# X-A4U-stick.net
KiCad netlist of a schematic drawn in EAGLE
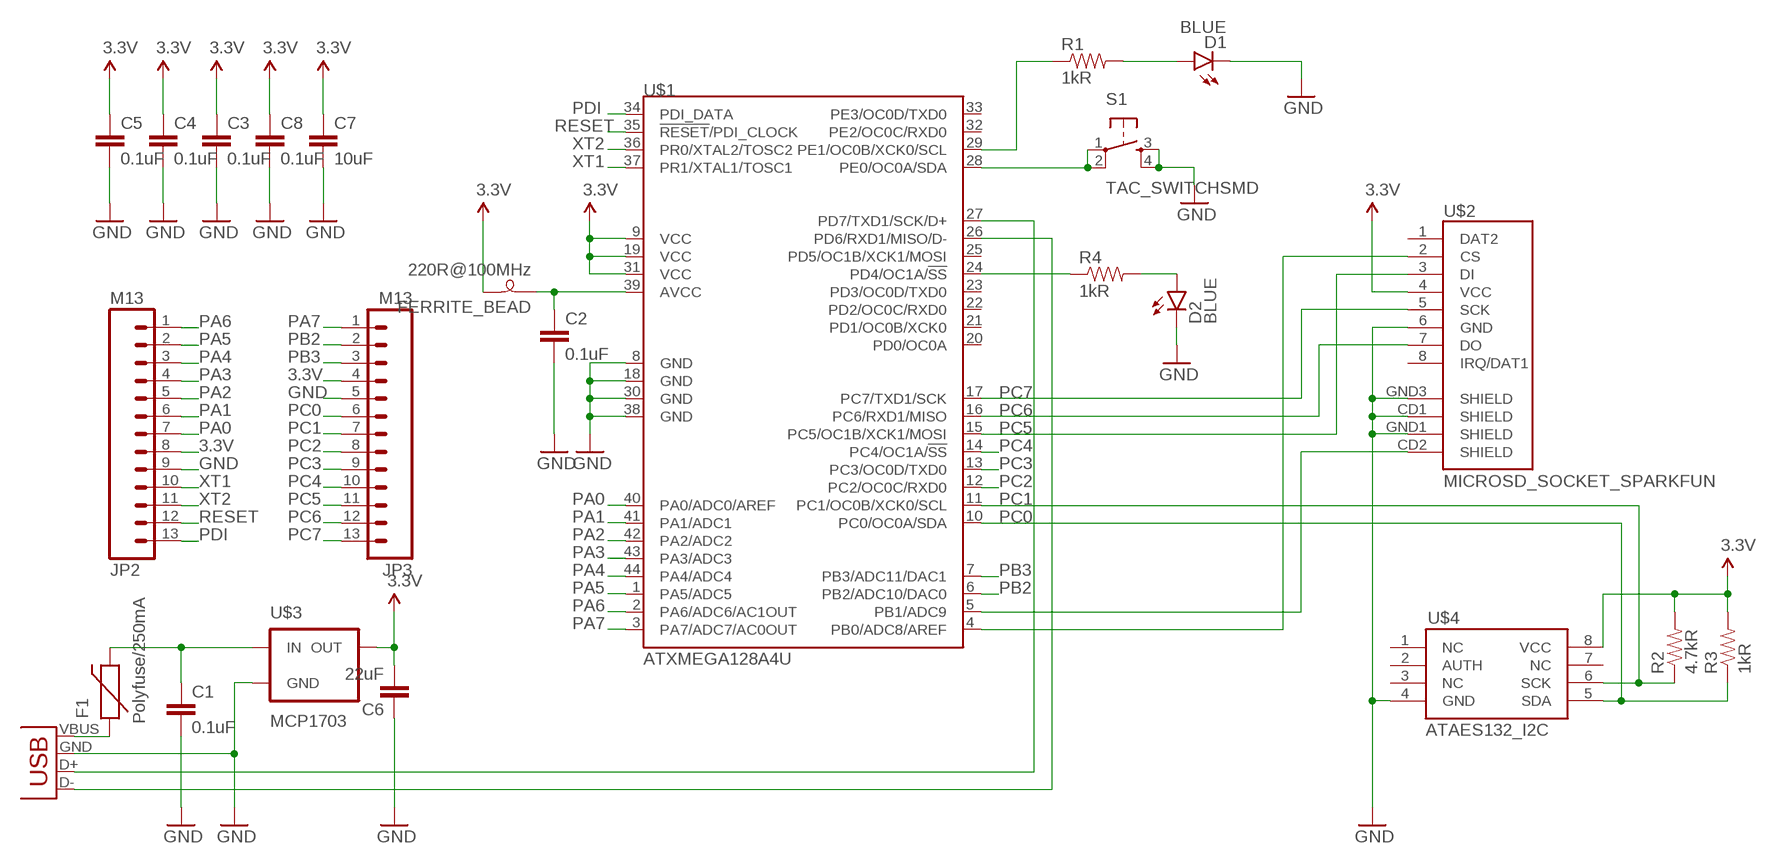
[diagram p0: schematic, sheet 1]

(export (version "E")
  (design (tool "Eeschema 10.0.6"))
  (components
    (comp (ref "C1")
      (value "0.1uF")
      (footprint "eagle-import:0805")
      (libsource (lib "eagle-import") (part "CAP0805"))
    )
    (comp (ref "C2")
      (value "0.1uF")
      (footprint "eagle-import:0805")
      (libsource (lib "eagle-import") (part "CAP0805"))
    )
    (comp (ref "C3")
      (value "0.1uF")
      (footprint "eagle-import:0805")
      (libsource (lib "eagle-import") (part "CAP0805"))
    )
    (comp (ref "C4")
      (value "0.1uF")
      (footprint "eagle-import:0805")
      (libsource (lib "eagle-import") (part "CAP0805"))
    )
    (comp (ref "C5")
      (value "0.1uF")
      (footprint "eagle-import:0805")
      (libsource (lib "eagle-import") (part "CAP0805"))
    )
    (comp (ref "C6")
      (value "22uF")
      (footprint "eagle-import:1206")
      (libsource (lib "eagle-import") (part "CAP1206"))
    )
    (comp (ref "C7")
      (value "10uF")
      (footprint "eagle-import:1206")
      (libsource (lib "eagle-import") (part "CAP1206"))
    )
    (comp (ref "C8")
      (value "0.1uF")
      (footprint "eagle-import:1206")
      (libsource (lib "eagle-import") (part "CAP1206"))
    )
    (comp (ref "D1")
      (value "BLUE")
      (footprint "eagle-import:LED-1206")
      (libsource (lib "eagle-import") (part "LED-BLUE1206"))
    )
    (comp (ref "D2")
      (value "BLUE")
      (footprint "eagle-import:LED-1206")
      (libsource (lib "eagle-import") (part "LED-BLUE1206"))
    )
    (comp (ref "F1")
      (value "Polyfuse/250mA")
      (footprint "eagle-import:PTC-1206-WIDE")
      (libsource (lib "eagle-import") (part "PTCSMD-W"))
    )
    (comp (ref "FERRITE_BEAD")
      (value "220R@100MHz")
      (footprint "eagle-import:0805")
      (libsource (lib "eagle-import") (part "FERRITE-BEAD0805"))
    )
    (comp (ref "JP1")
      (value "USB-A-H")
      (footprint "eagle-import:USB-A-H")
      (libsource (lib "eagle-import") (part "USB-A-H"))
    )
    (comp (ref "JP2")
      (value "M13")
      (footprint "eagle-import:1X13")
      (libsource (lib "eagle-import") (part "M13"))
    )
    (comp (ref "JP3")
      (value "M13")
      (footprint "eagle-import:1X13")
      (libsource (lib "eagle-import") (part "M13"))
    )
    (comp (ref "R1")
      (value "1kR")
      (footprint "eagle-import:1206")
      (libsource (lib "eagle-import") (part "RESISTOR1206"))
    )
    (comp (ref "R2")
      (value "4.7kR")
      (footprint "eagle-import:1206")
      (libsource (lib "eagle-import") (part "RESISTOR1206"))
    )
    (comp (ref "R3")
      (value "1kR")
      (footprint "eagle-import:1206")
      (libsource (lib "eagle-import") (part "RESISTOR1206"))
    )
    (comp (ref "R4")
      (value "1kR")
      (footprint "eagle-import:1206")
      (libsource (lib "eagle-import") (part "RESISTOR1206"))
    )
    (comp (ref "S1")
      (value "TAC_SWITCHSMD")
      (footprint "eagle-import:TACTILE-SWITCH-SMD")
      (libsource (lib "eagle-import") (part "TAC_SWITCHSMD"))
    )
    (comp (ref "U$1")
      (value "ATXMEGA128A4U")
      (footprint "eagle-import:TQFP-44")
      (libsource (lib "eagle-import") (part "ATXMEGA128A4U"))
    )
    (comp (ref "U$2")
      (value "MICROSD_SOCKET_SPARKFUN")
      (footprint "eagle-import:MICROSD_SOCKET_SPARKFUN")
      (libsource (lib "eagle-import") (part "MICROSD_SOCKET_SPARKFUN"))
    )
    (comp (ref "U$3")
      (value "MCP1703")
      (footprint "eagle-import:SOT-89")
      (libsource (lib "eagle-import") (part "MCP1703"))
    )
    (comp (ref "U$4")
      (value "ATAES132_I2C")
      (footprint "eagle-import:SOIC-8-NARROW")
      (libsource (lib "eagle-import") (part "ATAES132_I2C"))
    )
  )
  (nets
    (net (code "1") (name "/PA0") (class "Default")
      (node (ref "JP2") (pin "7") (pinfunction "7_7") (pintype "passive"))
      (node (ref "U$1") (pin "40") (pinfunction "PA0/ADC0/AREF_40") (pintype "bidirectional"))
    )
    (net (code "2") (name "/PA1") (class "Default")
      (node (ref "JP2") (pin "6") (pinfunction "6_6") (pintype "passive"))
      (node (ref "U$1") (pin "41") (pinfunction "PA1/ADC1_41") (pintype "bidirectional"))
    )
    (net (code "3") (name "/PA2") (class "Default")
      (node (ref "JP2") (pin "5") (pinfunction "5_5") (pintype "passive"))
      (node (ref "U$1") (pin "42") (pinfunction "PA2/ADC2_42") (pintype "bidirectional"))
    )
    (net (code "4") (name "/PA3") (class "Default")
      (node (ref "JP2") (pin "4") (pinfunction "4_4") (pintype "passive"))
      (node (ref "U$1") (pin "43") (pinfunction "PA3/ADC3_43") (pintype "bidirectional"))
    )
    (net (code "5") (name "/PA4") (class "Default")
      (node (ref "JP2") (pin "3") (pinfunction "3_3") (pintype "passive"))
      (node (ref "U$1") (pin "44") (pinfunction "PA4/ADC4_44") (pintype "bidirectional"))
    )
    (net (code "6") (name "/PA5") (class "Default")
      (node (ref "JP2") (pin "2") (pinfunction "2_2") (pintype "passive"))
      (node (ref "U$1") (pin "1") (pinfunction "PA5/ADC5_1") (pintype "bidirectional"))
    )
    (net (code "7") (name "/PA6") (class "Default")
      (node (ref "JP2") (pin "1") (pinfunction "1_1") (pintype "passive"))
      (node (ref "U$1") (pin "2") (pinfunction "PA6/ADC6/AC1OUT_2") (pintype "bidirectional"))
    )
    (net (code "8") (name "/PA7") (class "Default")
      (node (ref "JP3") (pin "1") (pinfunction "1_1") (pintype "passive"))
      (node (ref "U$1") (pin "3") (pinfunction "PA7/ADC7/AC0OUT_3") (pintype "bidirectional"))
    )
    (net (code "9") (name "/PB2") (class "Default")
      (node (ref "JP3") (pin "2") (pinfunction "2_2") (pintype "passive"))
      (node (ref "U$1") (pin "6") (pinfunction "PB2/ADC10/DAC0_6") (pintype "bidirectional"))
    )
    (net (code "10") (name "/PB3") (class "Default")
      (node (ref "JP3") (pin "3") (pinfunction "3_3") (pintype "passive"))
      (node (ref "U$1") (pin "7") (pinfunction "PB3/ADC11/DAC1_7") (pintype "bidirectional"))
    )
    (net (code "11") (name "/PC0") (class "Default")
      (node (ref "JP3") (pin "6") (pinfunction "6_6") (pintype "passive"))
      (node (ref "R3") (pin "1") (pinfunction "1_1") (pintype "passive"))
      (node (ref "U$1") (pin "10") (pinfunction "PC0/OC0A/SDA_10") (pintype "bidirectional"))
      (node (ref "U$4") (pin "5") (pinfunction "SDA_5") (pintype "bidirectional"))
    )
    (net (code "12") (name "/PC1") (class "Default")
      (node (ref "JP3") (pin "7") (pinfunction "7_7") (pintype "passive"))
      (node (ref "R2") (pin "1") (pinfunction "1_1") (pintype "passive"))
      (node (ref "U$1") (pin "11") (pinfunction "PC1/OC0B/XCK0/SCL_11") (pintype "bidirectional"))
      (node (ref "U$4") (pin "6") (pinfunction "SCK_6") (pintype "input"))
    )
    (net (code "13") (name "/PC2") (class "Default")
      (node (ref "JP3") (pin "8") (pinfunction "8_8") (pintype "passive"))
      (node (ref "U$1") (pin "12") (pinfunction "PC2/OC0C/RXD0_12") (pintype "bidirectional"))
    )
    (net (code "14") (name "/PC3") (class "Default")
      (node (ref "JP3") (pin "9") (pinfunction "9_9") (pintype "passive"))
      (node (ref "U$1") (pin "13") (pinfunction "PC3/OC0D/TXD0_13") (pintype "bidirectional"))
    )
    (net (code "15") (name "/PC4") (class "Default")
      (node (ref "JP3") (pin "10") (pinfunction "10_10") (pintype "passive"))
      (node (ref "U$1") (pin "14") (pinfunction "PC4/OC1A/~{SS}_14") (pintype "bidirectional"))
    )
    (net (code "16") (name "/PC5") (class "Default")
      (node (ref "JP3") (pin "11") (pinfunction "11_11") (pintype "passive"))
      (node (ref "U$1") (pin "15") (pinfunction "PC5/OC1B/XCK1/MOSI_15") (pintype "bidirectional"))
      (node (ref "U$2") (pin "3") (pinfunction "DI_3") (pintype "bidirectional"))
    )
    (net (code "17") (name "/PC6") (class "Default")
      (node (ref "JP3") (pin "12") (pinfunction "12_12") (pintype "passive"))
      (node (ref "U$1") (pin "16") (pinfunction "PC6/RXD1/MISO_16") (pintype "bidirectional"))
      (node (ref "U$2") (pin "7") (pinfunction "DO_7") (pintype "bidirectional"))
    )
    (net (code "18") (name "/PC7") (class "Default")
      (node (ref "JP3") (pin "13") (pinfunction "13_13") (pintype "passive"))
      (node (ref "U$1") (pin "17") (pinfunction "PC7/TXD1/SCK_17") (pintype "bidirectional"))
      (node (ref "U$2") (pin "5") (pinfunction "SCK_5") (pintype "bidirectional"))
    )
    (net (code "19") (name "/PDI") (class "Default")
      (node (ref "JP2") (pin "13") (pinfunction "13_13") (pintype "passive"))
      (node (ref "U$1") (pin "34") (pinfunction "PDI_DATA_34") (pintype "bidirectional"))
    )
    (net (code "20") (name "/RESET") (class "Default")
      (node (ref "JP2") (pin "12") (pinfunction "12_12") (pintype "passive"))
      (node (ref "U$1") (pin "35") (pinfunction "~{RESET}/PDI_CLOCK_35") (pintype "bidirectional"))
    )
    (net (code "21") (name "/XT1") (class "Default")
      (node (ref "JP2") (pin "10") (pinfunction "10_10") (pintype "passive"))
      (node (ref "U$1") (pin "37") (pinfunction "PR1/XTAL1/TOSC1_37") (pintype "bidirectional"))
    )
    (net (code "22") (name "/XT2") (class "Default")
      (node (ref "JP2") (pin "11") (pinfunction "11_11") (pintype "passive"))
      (node (ref "U$1") (pin "36") (pinfunction "PR0/XTAL2/TOSC2_36") (pintype "bidirectional"))
    )
    (net (code "23") (name "3.3V") (class "Default")
      (node (ref "C3") (pin "1") (pinfunction "1_1") (pintype "passive"))
      (node (ref "C4") (pin "1") (pinfunction "1_1") (pintype "passive"))
      (node (ref "C5") (pin "1") (pinfunction "1_1") (pintype "passive"))
      (node (ref "C6") (pin "2") (pinfunction "2_2") (pintype "passive"))
      (node (ref "C7") (pin "1") (pinfunction "1_1") (pintype "passive"))
      (node (ref "C8") (pin "1") (pinfunction "1_1") (pintype "passive"))
      (node (ref "FERRITE_BEAD") (pin "2") (pinfunction "2_2") (pintype "passive"))
      (node (ref "JP2") (pin "8") (pinfunction "8_8") (pintype "passive"))
      (node (ref "JP3") (pin "4") (pinfunction "4_4") (pintype "passive"))
      (node (ref "R2") (pin "2") (pinfunction "2_2") (pintype "passive"))
      (node (ref "R3") (pin "2") (pinfunction "2_2") (pintype "passive"))
      (node (ref "U$1") (pin "19") (pinfunction "VCC_19") (pintype "bidirectional"))
      (node (ref "U$1") (pin "31") (pinfunction "VCC_31") (pintype "bidirectional"))
      (node (ref "U$1") (pin "9") (pinfunction "VCC_9") (pintype "bidirectional"))
      (node (ref "U$2") (pin "4") (pinfunction "VCC_4") (pintype "bidirectional"))
      (node (ref "U$3") (pin "3") (pinfunction "OUT_3") (pintype "passive"))
      (node (ref "U$4") (pin "8") (pinfunction "VCC_8") (pintype "bidirectional"))
    )
    (net (code "24") (name "GND") (class "Default")
      (node (ref "C1") (pin "2") (pinfunction "2_2") (pintype "passive"))
      (node (ref "C2") (pin "2") (pinfunction "2_2") (pintype "passive"))
      (node (ref "C3") (pin "2") (pinfunction "2_2") (pintype "passive"))
      (node (ref "C4") (pin "2") (pinfunction "2_2") (pintype "passive"))
      (node (ref "C5") (pin "2") (pinfunction "2_2") (pintype "passive"))
      (node (ref "C6") (pin "1") (pinfunction "1_1") (pintype "passive"))
      (node (ref "C7") (pin "2") (pinfunction "2_2") (pintype "passive"))
      (node (ref "C8") (pin "2") (pinfunction "2_2") (pintype "passive"))
      (node (ref "D1") (pin "C") (pinfunction "C_C") (pintype "passive"))
      (node (ref "D2") (pin "C") (pinfunction "C_C") (pintype "passive"))
      (node (ref "JP1") (pin "GND") (pinfunction "VBUS_GND") (pintype "bidirectional"))
      (node (ref "JP2") (pin "9") (pinfunction "9_9") (pintype "passive"))
      (node (ref "JP3") (pin "5") (pinfunction "5_5") (pintype "passive"))
      (node (ref "S1") (pin "3") (pinfunction "3_3") (pintype "passive"))
      (node (ref "S1") (pin "4") (pinfunction "4_4") (pintype "passive"))
      (node (ref "U$1") (pin "18") (pinfunction "GND_18") (pintype "bidirectional"))
      (node (ref "U$1") (pin "30") (pinfunction "GND_30") (pintype "bidirectional"))
      (node (ref "U$1") (pin "38") (pinfunction "GND_38") (pintype "bidirectional"))
      (node (ref "U$1") (pin "8") (pinfunction "GND_8") (pintype "bidirectional"))
      (node (ref "U$2") (pin "6") (pinfunction "GND_6") (pintype "bidirectional"))
      (node (ref "U$2") (pin "CD1") (pinfunction "SHIELD_CD1") (pintype "bidirectional"))
      (node (ref "U$2") (pin "GND1") (pinfunction "SHIELD_GND1") (pintype "bidirectional"))
      (node (ref "U$2") (pin "GND3") (pinfunction "SHIELD_GND3") (pintype "bidirectional"))
      (node (ref "U$3") (pin "1") (pinfunction "GND_1") (pintype "input"))
      (node (ref "U$4") (pin "4") (pinfunction "GND_4") (pintype "bidirectional"))
    )
    (net (code "25") (name "Net-(C1-Pad1)") (class "Default")
      (node (ref "C1") (pin "1") (pinfunction "1_1") (pintype "passive"))
      (node (ref "F1") (pin "2") (pinfunction "2_2") (pintype "bidirectional"))
      (node (ref "U$3") (pin "2") (pinfunction "IN_2") (pintype "input"))
      (node (ref "U$3") (pin "4") (pinfunction "IN_4") (pintype "input"))
    )
    (net (code "26") (name "Net-(D1-PadA)") (class "Default")
      (node (ref "D1") (pin "A") (pinfunction "A_A") (pintype "passive"))
      (node (ref "R1") (pin "2") (pinfunction "2_2") (pintype "passive"))
    )
    (net (code "27") (name "Net-(D2-PadA)") (class "Default")
      (node (ref "D2") (pin "A") (pinfunction "A_A") (pintype "passive"))
      (node (ref "R4") (pin "2") (pinfunction "2_2") (pintype "passive"))
    )
    (net (code "28") (name "Net-(JP1-D+)") (class "Default")
      (node (ref "JP1") (pin "D-") (pinfunction "D+_D-") (pintype "bidirectional"))
      (node (ref "U$1") (pin "26") (pinfunction "PD6/RXD1/MISO/D-_26") (pintype "bidirectional"))
    )
    (net (code "29") (name "Net-(JP1-D-)") (class "Default")
      (node (ref "JP1") (pin "D+") (pinfunction "D-_D+") (pintype "bidirectional"))
      (node (ref "U$1") (pin "27") (pinfunction "PD7/TXD1/SCK/D+_27") (pintype "bidirectional"))
    )
    (net (code "30") (name "Net-(JP1-GND)") (class "Default")
      (node (ref "F1") (pin "1") (pinfunction "1_1") (pintype "bidirectional"))
      (node (ref "JP1") (pin "VBUS") (pinfunction "GND_VBUS") (pintype "bidirectional"))
    )
    (net (code "31") (name "Net-(U$1-AVCC)") (class "Default")
      (node (ref "C2") (pin "1") (pinfunction "1_1") (pintype "passive"))
      (node (ref "FERRITE_BEAD") (pin "1") (pinfunction "1_1") (pintype "passive"))
      (node (ref "U$1") (pin "39") (pinfunction "AVCC_39") (pintype "bidirectional"))
    )
    (net (code "32") (name "Net-(U$1-PB0{slash}ADC8{slash}AREF)") (class "Default")
      (node (ref "U$1") (pin "4") (pinfunction "PB0/ADC8/AREF_4") (pintype "bidirectional"))
      (node (ref "U$2") (pin "2") (pinfunction "CS_2") (pintype "bidirectional"))
    )
    (net (code "33") (name "Net-(U$1-PB1{slash}ADC9)") (class "Default")
      (node (ref "U$1") (pin "5") (pinfunction "PB1/ADC9_5") (pintype "bidirectional"))
      (node (ref "U$2") (pin "CD2") (pinfunction "SHIELD_CD2") (pintype "bidirectional"))
    )
    (net (code "34") (name "Net-(U$1-PD4{slash}OC1A{slash}~{SS})") (class "Default")
      (node (ref "R4") (pin "1") (pinfunction "1_1") (pintype "passive"))
      (node (ref "U$1") (pin "24") (pinfunction "PD4/OC1A/~{SS}_24") (pintype "bidirectional"))
    )
    (net (code "35") (name "Net-(U$1-PE0{slash}OC0A{slash}SDA)") (class "Default")
      (node (ref "S1") (pin "1") (pinfunction "1_1") (pintype "passive"))
      (node (ref "S1") (pin "2") (pinfunction "2_2") (pintype "passive"))
      (node (ref "U$1") (pin "28") (pinfunction "PE0/OC0A/SDA_28") (pintype "bidirectional"))
    )
    (net (code "36") (name "Net-(U$1-PE1{slash}OC0B{slash}XCK0{slash}SCL)") (class "Default")
      (node (ref "R1") (pin "1") (pinfunction "1_1") (pintype "passive"))
      (node (ref "U$1") (pin "29") (pinfunction "PE1/OC0B/XCK0/SCL_29") (pintype "bidirectional"))
    )
    (net (code "37") (name "unconnected-(U$1-PD0{slash}OC0A-Pad20)") (class "Default")
      (node (ref "U$1") (pin "20") (pinfunction "PD0/OC0A_20") (pintype "bidirectional"))
    )
    (net (code "38") (name "unconnected-(U$1-PD1{slash}OC0B{slash}XCK0-Pad21)") (class "Default")
      (node (ref "U$1") (pin "21") (pinfunction "PD1/OC0B/XCK0_21") (pintype "bidirectional"))
    )
    (net (code "39") (name "unconnected-(U$1-PD2{slash}OC0C{slash}RXD0-Pad22)") (class "Default")
      (node (ref "U$1") (pin "22") (pinfunction "PD2/OC0C/RXD0_22") (pintype "bidirectional"))
    )
    (net (code "40") (name "unconnected-(U$1-PD3{slash}OC0D{slash}TXD0-Pad23)") (class "Default")
      (node (ref "U$1") (pin "23") (pinfunction "PD3/OC0D/TXD0_23") (pintype "bidirectional"))
    )
    (net (code "41") (name "unconnected-(U$1-PD5{slash}OC1B{slash}XCK1{slash}MOSI-Pad25)") (class "Default")
      (node (ref "U$1") (pin "25") (pinfunction "PD5/OC1B/XCK1/MOSI_25") (pintype "bidirectional"))
    )
    (net (code "42") (name "unconnected-(U$1-PE2{slash}OC0C{slash}RXD0-Pad32)") (class "Default")
      (node (ref "U$1") (pin "32") (pinfunction "PE2/OC0C/RXD0_32") (pintype "bidirectional"))
    )
    (net (code "43") (name "unconnected-(U$1-PE3{slash}OC0D{slash}TXD0-Pad33)") (class "Default")
      (node (ref "U$1") (pin "33") (pinfunction "PE3/OC0D/TXD0_33") (pintype "bidirectional"))
    )
    (net (code "44") (name "unconnected-(U$2-DAT2-Pad1)") (class "Default")
      (node (ref "U$2") (pin "1") (pinfunction "DAT2_1") (pintype "bidirectional"))
    )
    (net (code "45") (name "unconnected-(U$2-IRQ{slash}DAT1-Pad8)") (class "Default")
      (node (ref "U$2") (pin "8") (pinfunction "IRQ/DAT1_8") (pintype "bidirectional"))
    )
    (net (code "46") (name "unconnected-(U$4-AUTH-Pad2)") (class "Default")
      (node (ref "U$4") (pin "2") (pinfunction "AUTH_2") (pintype "output"))
    )
    (net (code "47") (name "unconnected-(U$4-NC-Pad1)") (class "Default")
      (node (ref "U$4") (pin "1") (pinfunction "NC_1") (pintype "no_connect"))
    )
    (net (code "48") (name "unconnected-(U$4-NC-Pad3)") (class "Default")
      (node (ref "U$4") (pin "3") (pinfunction "NC_3") (pintype "no_connect"))
    )
    (net (code "49") (name "unconnected-(U$4-NC-Pad7)") (class "Default")
      (node (ref "U$4") (pin "7") (pinfunction "NC_7") (pintype "no_connect"))
    )
  )
)
